# yumingj2_eagle_assignment.net
KiCad netlist of a schematic drawn in EAGLE
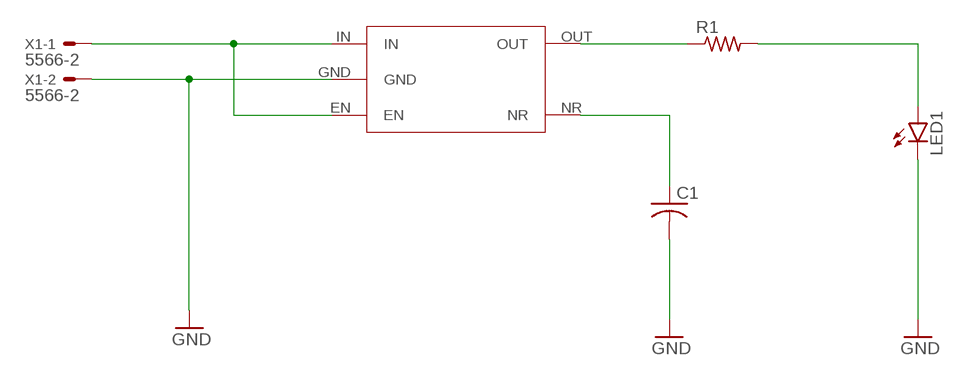
[diagram p0: schematic, sheet 1]

(export (version "E")
  (design (tool "Eeschema 10.0.6"))
  (components
    (comp (ref "C1")
      (value "C-US025-024X044")
      (footprint "eagle-import:C025-024X044")
      (libsource (lib "eagle-import") (part "C-US025-024X044"))
    )
    (comp (ref "LED1")
      (value "LEDLSU260")
      (footprint "eagle-import:LSU260")
      (libsource (lib "eagle-import") (part "LEDLSU260"))
    )
    (comp (ref "R1")
      (value "R-US_0204/7")
      (footprint "eagle-import:0204_7")
      (libsource (lib "eagle-import") (part "R-US_0204/7"))
    )
    (comp (ref "U$1")
      (value "TPS799")
      (footprint "eagle-import:TPS799")
      (libsource (lib "eagle-import") (part "TPS799"))
    )
    (comp (ref "X1")
      (value "5566-2")
      (footprint "eagle-import:5566-2")
      (fields (field (name "MF") "MOLEX"))
      (libsource (lib "eagle-import") (part "5566-2"))
    )
  )
  (nets
    (net (code "1") (name "GND") (class "Default")
      (node (ref "C1") (pin "2") (pinfunction "2_2") (pintype "passive"))
      (node (ref "LED1") (pin "K") (pinfunction "C_K") (pintype "passive"))
      (node (ref "U$1") (pin "GND") (pinfunction "GND_GND") (pintype "bidirectional"))
      (node (ref "X1") (pin "2") (pinfunction "S_2") (pintype "passive"))
    )
    (net (code "2") (name "Net-(C1-Pad1)") (class "Default")
      (node (ref "C1") (pin "1") (pinfunction "1_1") (pintype "passive"))
      (node (ref "U$1") (pin "NR") (pinfunction "NR_NR") (pintype "bidirectional"))
    )
    (net (code "3") (name "Net-(LED1-PadA)") (class "Default")
      (node (ref "LED1") (pin "A") (pinfunction "A_A") (pintype "passive"))
      (node (ref "R1") (pin "2") (pinfunction "2_2") (pintype "passive"))
    )
    (net (code "4") (name "Net-(R1-Pad1)") (class "Default")
      (node (ref "R1") (pin "1") (pinfunction "1_1") (pintype "passive"))
      (node (ref "U$1") (pin "OUT") (pinfunction "OUT_OUT") (pintype "bidirectional"))
    )
    (net (code "5") (name "Net-(X1A-S)") (class "Default")
      (node (ref "U$1") (pin "EN") (pinfunction "EN_EN") (pintype "bidirectional"))
      (node (ref "U$1") (pin "IN") (pinfunction "IN_IN") (pintype "bidirectional"))
      (node (ref "X1") (pin "1") (pinfunction "S_1") (pintype "passive"))
    )
  )
)
